# ProPrj_BAP_PCB_Surgeon_2025-11-06.net
KiCad netlist of a schematic drawn in EasyEDA Pro
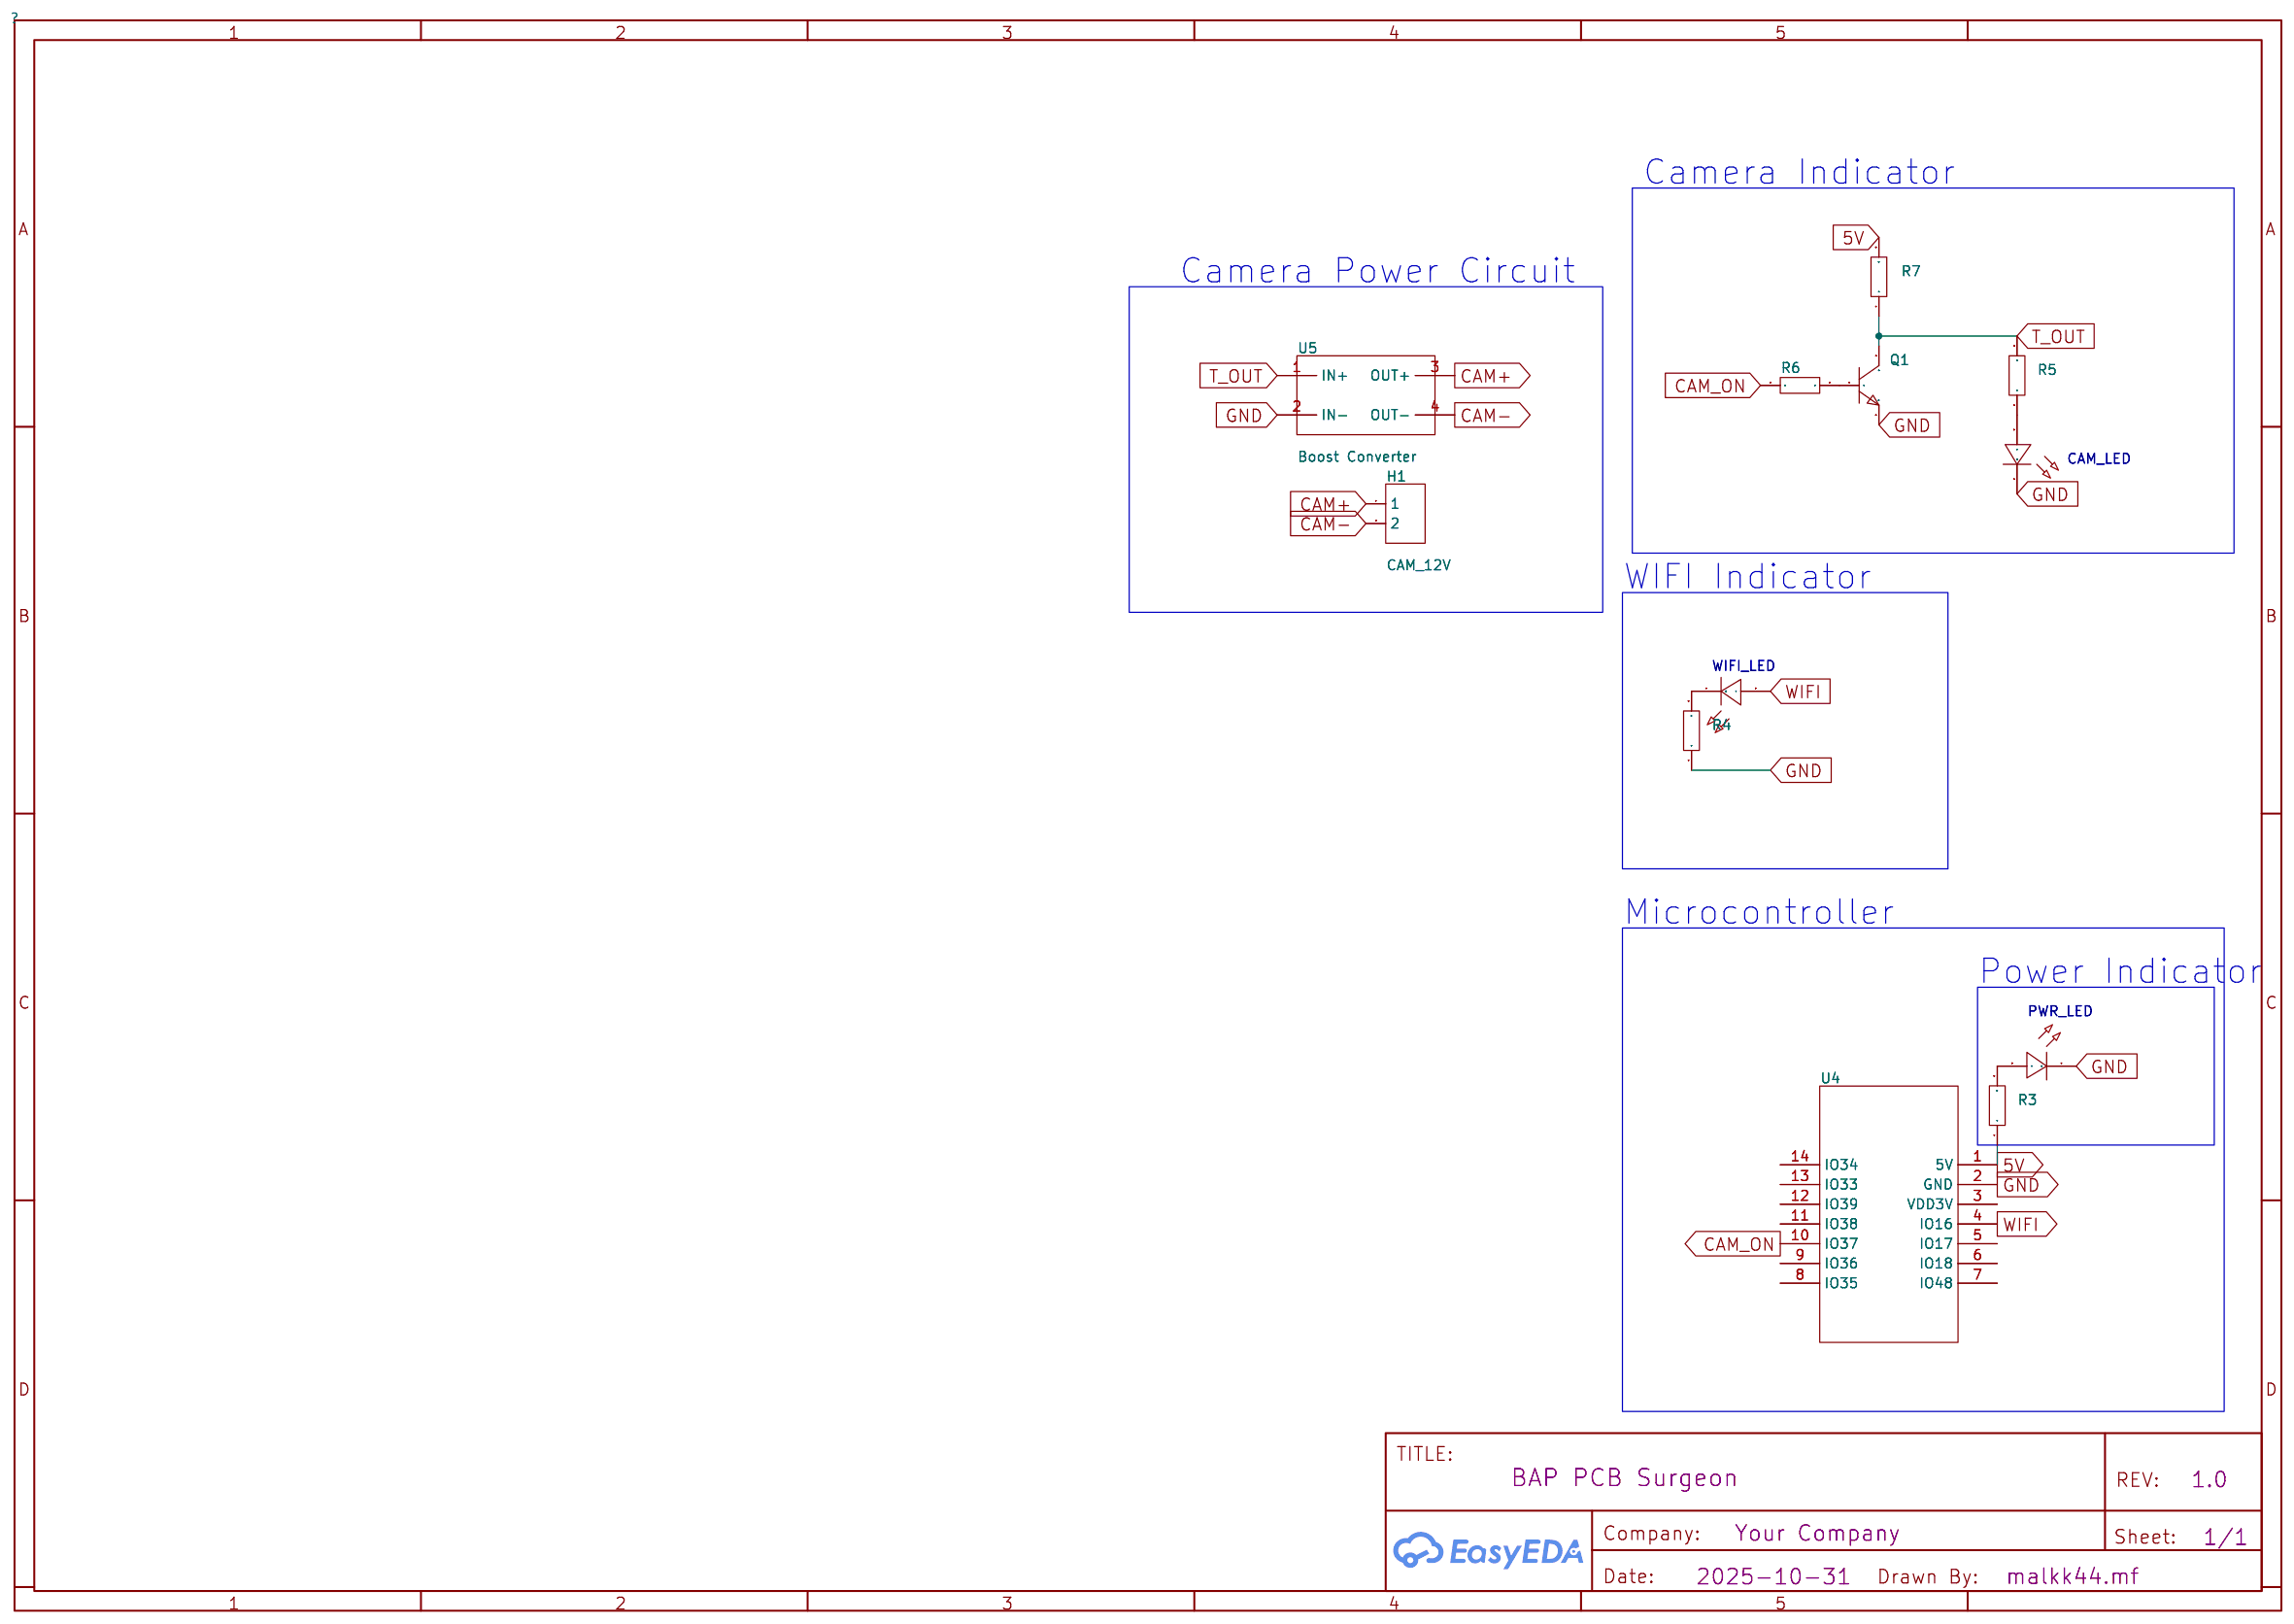
[diagram p0: schematic sheet]

(export (version "E")
  (design (tool "Eeschema 10.0.6"))
  (components
    (comp (ref "CAM_LED")
      (value "~")
      (footprint "easyedapro:LED_0603")
      (libsource (lib "easyedapro") (part "LED_G"))
    )
    (comp (ref "H1")
      (value "CAM_12V")
      (footprint "easyedapro:HDR-TH_2P-P2.54-V-F")
      (libsource (lib "easyedapro") (part "Header-Female-2.54_1x2"))
    )
    (comp (ref "PWR_LED")
      (value "~")
      (footprint "easyedapro:LED_0603")
      (libsource (lib "easyedapro") (part "LED_G"))
    )
    (comp (ref "Q1")
      (value "~")
      (footprint "easyedapro:S8050_SOT-23")
      (libsource (lib "easyedapro") (part "NPN"))
    )
    (comp (ref "R3")
      (value "330Ω")
      (footprint "easyedapro:RES-TH_BD2.2-L6.5-P10.50-D0.6")
      (fields (field (name "Manufacturer Part") "MFR-25FTE52-330R") (field (name "Manufacturer") "YAGEO(国巨)"))
      (libsource (lib "easyedapro") (part "MFR-25FTE52-330R"))
    )
    (comp (ref "R4")
      (value "330Ω")
      (footprint "easyedapro:RES-TH_BD2.2-L6.5-P10.50-D0.6")
      (fields (field (name "Manufacturer Part") "MFR-25FTE52-330R") (field (name "Manufacturer") "YAGEO(国巨)"))
      (libsource (lib "easyedapro") (part "MFR-25FTE52-330R"))
    )
    (comp (ref "R5")
      (value "330Ω")
      (footprint "easyedapro:RES-TH_BD2.2-L6.5-P10.50-D0.6")
      (fields (field (name "Manufacturer Part") "MFR-25FTE52-330R") (field (name "Manufacturer") "YAGEO(国巨)"))
      (libsource (lib "easyedapro") (part "MFR-25FTE52-330R"))
    )
    (comp (ref "R6")
      (value "~")
      (footprint "easyedapro:Resistor 1/8w 7mm metal film")
      (fields
        (field (name "Manufacturer Part") "1206W4F1002T5E")
        (field (name "Manufacturer") "UNI-ROYAL(Uniroyal Elec)")
      )
      (libsource (lib "easyedapro") (part "resistor"))
    )
    (comp (ref "R7")
      (value "~")
      (footprint "easyedapro:Resistor 1/8w 7mm metal film")
      (fields
        (field (name "Manufacturer Part") "1206W4F1002T5E")
        (field (name "Manufacturer") "UNI-ROYAL(Uniroyal Elec)")
      )
      (libsource (lib "easyedapro") (part "resistor"))
    )
    (comp (ref "U4")
      (value "~")
      (footprint "easyedapro:LilyGO TQ-T Pro")
      (libsource (lib "easyedapro") (part "LilyGO TQ-T Pro"))
    )
    (comp (ref "U5")
      (value "Boost Converter")
      (footprint "easyedapro:Boost Converter")
      (libsource (lib "easyedapro") (part "Boost Converter"))
    )
    (comp (ref "WIFI_LED")
      (value "~")
      (footprint "easyedapro:LED_0603")
      (libsource (lib "easyedapro") (part "LED_G"))
    )
  )
  (nets
    (net (code "1") (name "5V") (class "Default")
      (node (ref "R3") (pin "1") (pinfunction "1_1") (pintype "input"))
      (node (ref "R7") (pin "2") (pinfunction "2_2") (pintype "input"))
      (node (ref "U4") (pin "1") (pinfunction "5V_1") (pintype "output"))
    )
    (net (code "2") (name "CAM+") (class "Default")
      (node (ref "H1") (pin "1") (pinfunction "1_1") (pintype "input"))
      (node (ref "U5") (pin "3") (pinfunction "OUT+_3") (pintype "output"))
    )
    (net (code "3") (name "CAM-") (class "Default")
      (node (ref "H1") (pin "2") (pinfunction "2_2") (pintype "input"))
      (node (ref "U5") (pin "4") (pinfunction "OUT-_4") (pintype "output"))
    )
    (net (code "4") (name "CAM_ON") (class "Default")
      (node (ref "R6") (pin "1") (pinfunction "1_1") (pintype "input"))
      (node (ref "U4") (pin "10") (pinfunction "IO37_10") (pintype "bidirectional"))
    )
    (net (code "5") (name "GND") (class "Default")
      (node (ref "CAM_LED") (pin "1") (pinfunction "C_1") (pintype "input"))
      (node (ref "PWR_LED") (pin "1") (pinfunction "C_1") (pintype "input"))
      (node (ref "Q1") (pin "2") (pinfunction "2_2") (pintype "unspecified"))
      (node (ref "R4") (pin "1") (pinfunction "1_1") (pintype "input"))
      (node (ref "U4") (pin "2") (pinfunction "GND_2") (pintype "output"))
      (node (ref "U5") (pin "2") (pinfunction "IN-_2") (pintype "input"))
    )
    (net (code "6") (name "Net-(CAM_LED-A)") (class "Default")
      (node (ref "CAM_LED") (pin "2") (pinfunction "A_2") (pintype "input"))
      (node (ref "R5") (pin "1") (pinfunction "1_1") (pintype "input"))
    )
    (net (code "7") (name "Net-(PWR_LED-A)") (class "Default")
      (node (ref "PWR_LED") (pin "2") (pinfunction "A_2") (pintype "input"))
      (node (ref "R3") (pin "2") (pinfunction "2_2") (pintype "input"))
    )
    (net (code "8") (name "Net-(Q1-Pad1)") (class "Default")
      (node (ref "Q1") (pin "1") (pinfunction "1_1") (pintype "unspecified"))
      (node (ref "R6") (pin "2") (pinfunction "2_2") (pintype "input"))
    )
    (net (code "9") (name "Net-(WIFI_LED-C)") (class "Default")
      (node (ref "R4") (pin "2") (pinfunction "2_2") (pintype "input"))
      (node (ref "WIFI_LED") (pin "1") (pinfunction "C_1") (pintype "input"))
    )
    (net (code "10") (name "T_OUT") (class "Default")
      (node (ref "Q1") (pin "3") (pinfunction "3_3") (pintype "unspecified"))
      (node (ref "R5") (pin "2") (pinfunction "2_2") (pintype "input"))
      (node (ref "R7") (pin "1") (pinfunction "1_1") (pintype "input"))
      (node (ref "U5") (pin "1") (pinfunction "IN+_1") (pintype "input"))
    )
    (net (code "11") (name "WIFI") (class "Default")
      (node (ref "U4") (pin "4") (pinfunction "IO16_4") (pintype "bidirectional"))
      (node (ref "WIFI_LED") (pin "2") (pinfunction "A_2") (pintype "input"))
    )
    (net (code "12") (name "unconnected-(U4-IO17-Pad5)") (class "Default")
      (node (ref "U4") (pin "5") (pinfunction "IO17_5") (pintype "bidirectional"))
    )
    (net (code "13") (name "unconnected-(U4-IO18-Pad6)") (class "Default")
      (node (ref "U4") (pin "6") (pinfunction "IO18_6") (pintype "bidirectional"))
    )
    (net (code "14") (name "unconnected-(U4-IO33-Pad13)") (class "Default")
      (node (ref "U4") (pin "13") (pinfunction "IO33_13") (pintype "bidirectional"))
    )
    (net (code "15") (name "unconnected-(U4-IO34-Pad14)") (class "Default")
      (node (ref "U4") (pin "14") (pinfunction "IO34_14") (pintype "bidirectional"))
    )
    (net (code "16") (name "unconnected-(U4-IO35-Pad8)") (class "Default")
      (node (ref "U4") (pin "8") (pinfunction "IO35_8") (pintype "bidirectional"))
    )
    (net (code "17") (name "unconnected-(U4-IO36-Pad9)") (class "Default")
      (node (ref "U4") (pin "9") (pinfunction "IO36_9") (pintype "bidirectional"))
    )
    (net (code "18") (name "unconnected-(U4-IO38-Pad11)") (class "Default")
      (node (ref "U4") (pin "11") (pinfunction "IO38_11") (pintype "bidirectional"))
    )
    (net (code "19") (name "unconnected-(U4-IO39-Pad12)") (class "Default")
      (node (ref "U4") (pin "12") (pinfunction "IO39_12") (pintype "bidirectional"))
    )
    (net (code "20") (name "unconnected-(U4-IO48-Pad7)") (class "Default")
      (node (ref "U4") (pin "7") (pinfunction "IO48_7") (pintype "bidirectional"))
    )
    (net (code "21") (name "unconnected-(U4-VDD3V-Pad3)") (class "Default")
      (node (ref "U4") (pin "3") (pinfunction "VDD3V_3") (pintype "output"))
    )
  )
)
